# Powerswitch_2_Dioda_dan_MPU6050_v2.net
KiCad netlist of a schematic drawn in EAGLE
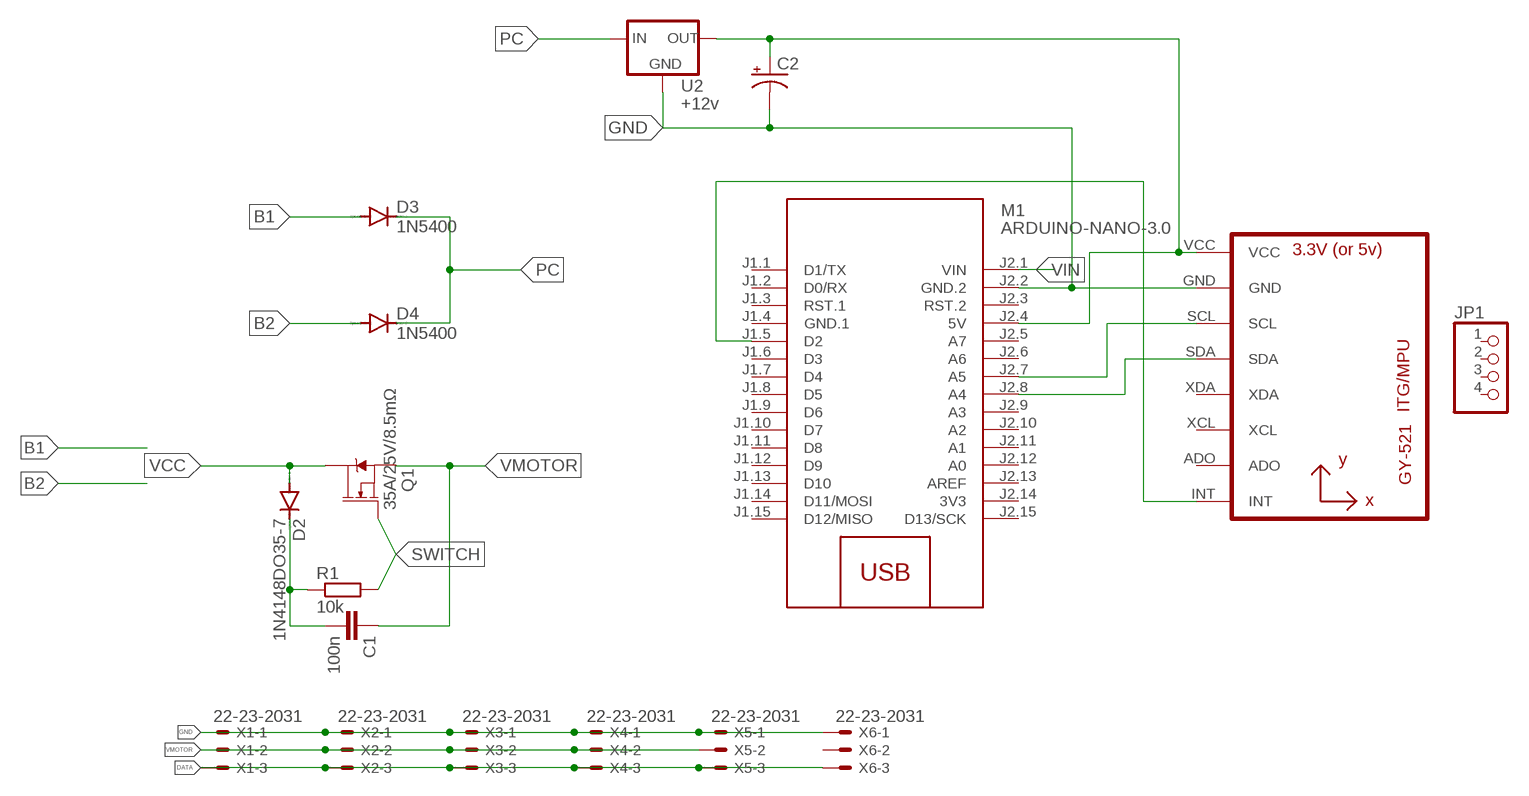
[diagram p0: schematic, sheet 1]

(export (version "E")
  (design (tool "Eeschema 10.0.6"))
  (components
    (comp (ref "C1")
      (value "100n")
      (footprint "eagle-import:C025-030X050")
      (libsource (lib "eagle-import") (part "C-EU025-030X050"))
    )
    (comp (ref "C2")
      (value "CPOL-USE2-5")
      (footprint "eagle-import:E2-5")
      (libsource (lib "eagle-import") (part "CPOL-USE2-5"))
    )
    (comp (ref "D2")
      (value "1N4148DO35-7")
      (footprint "eagle-import:DO35-7")
      (libsource (lib "eagle-import") (part "1N4148DO35-7"))
    )
    (comp (ref "D3")
      (value "1N5400")
      (footprint "eagle-import:DO201-15")
      (libsource (lib "eagle-import") (part "1N5400"))
    )
    (comp (ref "D4")
      (value "1N5400")
      (footprint "eagle-import:DO201-15")
      (libsource (lib "eagle-import") (part "1N5400"))
    )
    (comp (ref "JP1")
      (value "PINHD-1X4")
      (footprint "eagle-import:1X04")
      (libsource (lib "eagle-import") (part "PINHD-1X4"))
    )
    (comp (ref "M1")
      (value "ARDUINO-NANO-3.0")
      (footprint "eagle-import:ARDUINO-NANO-3.0")
      (libsource (lib "eagle-import") (part "ARDUINO-NANO-3.0"))
    )
    (comp (ref "Q1")
      (value "35A/25V/8.5mΩ")
      (footprint "eagle-import:DPAK")
      (libsource (lib "eagle-import") (part "MOSFET-NCH-FDD8780"))
    )
    (comp (ref "R1")
      (value "10k")
      (footprint "eagle-import:R1206")
      (libsource (lib "eagle-import") (part "R-EU_R1206"))
    )
    (comp (ref "U1")
      (value "GY-521MPU6050")
      (footprint "eagle-import:GY-521")
      (libsource (lib "eagle-import") (part "GY-521MPU6050"))
    )
    (comp (ref "U2")
      (value "+12v")
      (footprint "eagle-import:TO-252")
      (libsource (lib "eagle-import") (part "V_REG_78XX7812"))
    )
    (comp (ref "X1")
      (value "22-23-2031")
      (footprint "eagle-import:22-23-2031")
      (fields (field (name "MF") "MOLEX"))
      (libsource (lib "eagle-import") (part "22-23-2031"))
    )
    (comp (ref "X2")
      (value "22-23-2031")
      (footprint "eagle-import:22-23-2031")
      (fields (field (name "MF") "MOLEX"))
      (libsource (lib "eagle-import") (part "22-23-2031"))
    )
    (comp (ref "X3")
      (value "22-23-2031")
      (footprint "eagle-import:22-23-2031")
      (fields (field (name "MF") "MOLEX"))
      (libsource (lib "eagle-import") (part "22-23-2031"))
    )
    (comp (ref "X4")
      (value "22-23-2031")
      (footprint "eagle-import:22-23-2031")
      (fields (field (name "MF") "MOLEX"))
      (libsource (lib "eagle-import") (part "22-23-2031"))
    )
    (comp (ref "X5")
      (value "22-23-2031")
      (footprint "eagle-import:22-23-2031")
      (fields (field (name "MF") "MOLEX"))
      (libsource (lib "eagle-import") (part "22-23-2031"))
    )
    (comp (ref "X6")
      (value "22-23-2031")
      (footprint "eagle-import:22-23-2031")
      (fields (field (name "MF") "MOLEX"))
      (libsource (lib "eagle-import") (part "22-23-2031"))
    )
  )
  (nets
    (net (code "1") (name "/3V3") (class "Default")
      (node (ref "M1") (pin "J2.14") (pinfunction "3V3_J2.14") (pintype "power_in"))
    )
    (net (code "2") (name "/GND.1") (class "Default")
      (node (ref "M1") (pin "J1.4") (pinfunction "GND.1_J1.4") (pintype "power_in"))
    )
    (net (code "3") (name "B1") (class "Default")
      (node (ref "D3") (pin "A") (pinfunction "A_A") (pintype "passive"))
    )
    (net (code "4") (name "B2") (class "Default")
      (node (ref "D4") (pin "A") (pinfunction "A_A") (pintype "passive"))
    )
    (net (code "5") (name "DATA") (class "Default")
      (node (ref "X1") (pin "3") (pinfunction "S_3") (pintype "passive"))
      (node (ref "X2") (pin "3") (pinfunction "S_3") (pintype "passive"))
      (node (ref "X3") (pin "3") (pinfunction "S_3") (pintype "passive"))
      (node (ref "X4") (pin "3") (pinfunction "S_3") (pintype "passive"))
      (node (ref "X5") (pin "3") (pinfunction "S_3") (pintype "passive"))
      (node (ref "X6") (pin "3") (pinfunction "S_3") (pintype "passive"))
    )
    (net (code "6") (name "GND") (class "Default")
      (node (ref "C2") (pin "-") (pinfunction "-_-") (pintype "passive"))
      (node (ref "M1") (pin "J2.2") (pinfunction "GND.2_J2.2") (pintype "power_in"))
      (node (ref "U1") (pin "GND") (pinfunction "GND_GND") (pintype "bidirectional"))
      (node (ref "U2") (pin "3") (pinfunction "GND_3") (pintype "input"))
      (node (ref "X1") (pin "1") (pinfunction "S_1") (pintype "passive"))
      (node (ref "X2") (pin "1") (pinfunction "S_1") (pintype "passive"))
      (node (ref "X3") (pin "1") (pinfunction "S_1") (pintype "passive"))
      (node (ref "X4") (pin "1") (pinfunction "S_1") (pintype "passive"))
      (node (ref "X5") (pin "1") (pinfunction "S_1") (pintype "passive"))
      (node (ref "X6") (pin "1") (pinfunction "S_1") (pintype "passive"))
    )
    (net (code "7") (name "Net-(C1-Pad2)") (class "Default")
      (node (ref "C1") (pin "2") (pinfunction "2_2") (pintype "passive"))
      (node (ref "D2") (pin "C") (pinfunction "C_C") (pintype "passive"))
      (node (ref "R1") (pin "1") (pinfunction "1_1") (pintype "passive"))
    )
    (net (code "8") (name "Net-(M1-5V)") (class "Default")
      (node (ref "C2") (pin "+") (pinfunction "+_+") (pintype "passive"))
      (node (ref "M1") (pin "J2.4") (pinfunction "5V_J2.4") (pintype "power_in"))
      (node (ref "U1") (pin "VCC") (pinfunction "VCC_VCC") (pintype "bidirectional"))
      (node (ref "U2") (pin "2") (pinfunction "OUT_2") (pintype "passive"))
    )
    (net (code "9") (name "Net-(M1-A4)") (class "Default")
      (node (ref "M1") (pin "J2.8") (pinfunction "A4_J2.8") (pintype "bidirectional"))
      (node (ref "U1") (pin "SDA") (pinfunction "SDA_SDA") (pintype "bidirectional"))
    )
    (net (code "10") (name "Net-(M1-A5)") (class "Default")
      (node (ref "M1") (pin "J2.7") (pinfunction "A5_J2.7") (pintype "bidirectional"))
      (node (ref "U1") (pin "SCL") (pinfunction "SCL_SCL") (pintype "bidirectional"))
    )
    (net (code "11") (name "Net-(M1-D2)") (class "Default")
      (node (ref "M1") (pin "J1.5") (pinfunction "D2_J1.5") (pintype "bidirectional"))
      (node (ref "U1") (pin "INT") (pinfunction "INT_INT") (pintype "bidirectional"))
    )
    (net (code "12") (name "PC") (class "Default")
      (node (ref "D3") (pin "C") (pinfunction "C_C") (pintype "passive"))
      (node (ref "D4") (pin "C") (pinfunction "C_C") (pintype "passive"))
      (node (ref "U2") (pin "1") (pinfunction "IN_1") (pintype "input"))
    )
    (net (code "13") (name "SWITCH") (class "Default")
      (node (ref "Q1") (pin "1") (pinfunction "G_1") (pintype "bidirectional"))
      (node (ref "R1") (pin "2") (pinfunction "2_2") (pintype "passive"))
    )
    (net (code "14") (name "VCC") (class "Default")
      (node (ref "D2") (pin "A") (pinfunction "A_A") (pintype "passive"))
      (node (ref "Q1") (pin "4") (pinfunction "D_4") (pintype "bidirectional"))
    )
    (net (code "15") (name "VIN") (class "Default")
      (node (ref "M1") (pin "J2.1") (pinfunction "VIN_J2.1") (pintype "power_in"))
    )
    (net (code "16") (name "VMOTOR") (class "Default")
      (node (ref "C1") (pin "1") (pinfunction "1_1") (pintype "passive"))
      (node (ref "Q1") (pin "3") (pinfunction "S_3") (pintype "bidirectional"))
      (node (ref "X1") (pin "2") (pinfunction "S_2") (pintype "passive"))
      (node (ref "X2") (pin "2") (pinfunction "S_2") (pintype "passive"))
      (node (ref "X3") (pin "2") (pinfunction "S_2") (pintype "passive"))
      (node (ref "X4") (pin "2") (pinfunction "S_2") (pintype "passive"))
      (node (ref "X5") (pin "2") (pinfunction "S_2") (pintype "passive"))
    )
    (net (code "17") (name "unconnected-(JP1-Pad1)") (class "Default")
      (node (ref "JP1") (pin "1") (pinfunction "1_1") (pintype "passive"))
    )
    (net (code "18") (name "unconnected-(JP1-Pad2)") (class "Default")
      (node (ref "JP1") (pin "2") (pinfunction "2_2") (pintype "passive"))
    )
    (net (code "19") (name "unconnected-(JP1-Pad3)") (class "Default")
      (node (ref "JP1") (pin "3") (pinfunction "3_3") (pintype "passive"))
    )
    (net (code "20") (name "unconnected-(JP1-Pad4)") (class "Default")
      (node (ref "JP1") (pin "4") (pinfunction "4_4") (pintype "passive"))
    )
    (net (code "21") (name "unconnected-(M1-A0-PadJ2.12)") (class "Default")
      (node (ref "M1") (pin "J2.12") (pinfunction "A0_J2.12") (pintype "bidirectional"))
    )
    (net (code "22") (name "unconnected-(M1-A1-PadJ2.11)") (class "Default")
      (node (ref "M1") (pin "J2.11") (pinfunction "A1_J2.11") (pintype "bidirectional"))
    )
    (net (code "23") (name "unconnected-(M1-A2-PadJ2.10)") (class "Default")
      (node (ref "M1") (pin "J2.10") (pinfunction "A2_J2.10") (pintype "bidirectional"))
    )
    (net (code "24") (name "unconnected-(M1-A3-PadJ2.9)") (class "Default")
      (node (ref "M1") (pin "J2.9") (pinfunction "A3_J2.9") (pintype "bidirectional"))
    )
    (net (code "25") (name "unconnected-(M1-A6-PadJ2.6)") (class "Default")
      (node (ref "M1") (pin "J2.6") (pinfunction "A6_J2.6") (pintype "bidirectional"))
    )
    (net (code "26") (name "unconnected-(M1-A7-PadJ2.5)") (class "Default")
      (node (ref "M1") (pin "J2.5") (pinfunction "A7_J2.5") (pintype "bidirectional"))
    )
    (net (code "27") (name "unconnected-(M1-AREF-PadJ2.13)") (class "Default")
      (node (ref "M1") (pin "J2.13") (pinfunction "AREF_J2.13") (pintype "bidirectional"))
    )
    (net (code "28") (name "unconnected-(M1-D0{slash}RX-PadJ1.2)") (class "Default")
      (node (ref "M1") (pin "J1.2") (pinfunction "D0/RX_J1.2") (pintype "bidirectional"))
    )
    (net (code "29") (name "unconnected-(M1-D1{slash}TX-PadJ1.1)") (class "Default")
      (node (ref "M1") (pin "J1.1") (pinfunction "D1/TX_J1.1") (pintype "bidirectional"))
    )
    (net (code "30") (name "unconnected-(M1-D3-PadJ1.6)") (class "Default")
      (node (ref "M1") (pin "J1.6") (pinfunction "D3_J1.6") (pintype "bidirectional"))
    )
    (net (code "31") (name "unconnected-(M1-D4-PadJ1.7)") (class "Default")
      (node (ref "M1") (pin "J1.7") (pinfunction "D4_J1.7") (pintype "bidirectional"))
    )
    (net (code "32") (name "unconnected-(M1-D5-PadJ1.8)") (class "Default")
      (node (ref "M1") (pin "J1.8") (pinfunction "D5_J1.8") (pintype "bidirectional"))
    )
    (net (code "33") (name "unconnected-(M1-D6-PadJ1.9)") (class "Default")
      (node (ref "M1") (pin "J1.9") (pinfunction "D6_J1.9") (pintype "bidirectional"))
    )
    (net (code "34") (name "unconnected-(M1-D7-PadJ1.10)") (class "Default")
      (node (ref "M1") (pin "J1.10") (pinfunction "D7_J1.10") (pintype "bidirectional"))
    )
    (net (code "35") (name "unconnected-(M1-D8-PadJ1.11)") (class "Default")
      (node (ref "M1") (pin "J1.11") (pinfunction "D8_J1.11") (pintype "bidirectional"))
    )
    (net (code "36") (name "unconnected-(M1-D9-PadJ1.12)") (class "Default")
      (node (ref "M1") (pin "J1.12") (pinfunction "D9_J1.12") (pintype "bidirectional"))
    )
    (net (code "37") (name "unconnected-(M1-D10-PadJ1.13)") (class "Default")
      (node (ref "M1") (pin "J1.13") (pinfunction "D10_J1.13") (pintype "bidirectional"))
    )
    (net (code "38") (name "unconnected-(M1-D11{slash}MOSI-PadJ1.14)") (class "Default")
      (node (ref "M1") (pin "J1.14") (pinfunction "D11/MOSI_J1.14") (pintype "bidirectional"))
    )
    (net (code "39") (name "unconnected-(M1-D12{slash}MISO-PadJ1.15)") (class "Default")
      (node (ref "M1") (pin "J1.15") (pinfunction "D12/MISO_J1.15") (pintype "bidirectional"))
    )
    (net (code "40") (name "unconnected-(M1-D13{slash}SCK-PadJ2.15)") (class "Default")
      (node (ref "M1") (pin "J2.15") (pinfunction "D13/SCK_J2.15") (pintype "bidirectional"))
    )
    (net (code "41") (name "unconnected-(M1-RST.1-PadJ1.3)") (class "Default")
      (node (ref "M1") (pin "J1.3") (pinfunction "RST.1_J1.3") (pintype "bidirectional"))
    )
    (net (code "42") (name "unconnected-(M1-RST.2-PadJ2.3)") (class "Default")
      (node (ref "M1") (pin "J2.3") (pinfunction "RST.2_J2.3") (pintype "bidirectional"))
    )
    (net (code "43") (name "unconnected-(U1-PadADO)") (class "Default")
      (node (ref "U1") (pin "ADO") (pinfunction "ADO_ADO") (pintype "bidirectional"))
    )
    (net (code "44") (name "unconnected-(U1-PadXCL)") (class "Default")
      (node (ref "U1") (pin "XCL") (pinfunction "XCL_XCL") (pintype "bidirectional"))
    )
    (net (code "45") (name "unconnected-(U1-PadXDA)") (class "Default")
      (node (ref "U1") (pin "XDA") (pinfunction "XDA_XDA") (pintype "bidirectional"))
    )
    (net (code "46") (name "unconnected-(X6B-S-Pad2)") (class "Default")
      (node (ref "X6") (pin "2") (pinfunction "S_2") (pintype "passive"))
    )
  )
)
